# LIGHT-TDS.net
KiCad netlist of a schematic drawn in Altium Designer
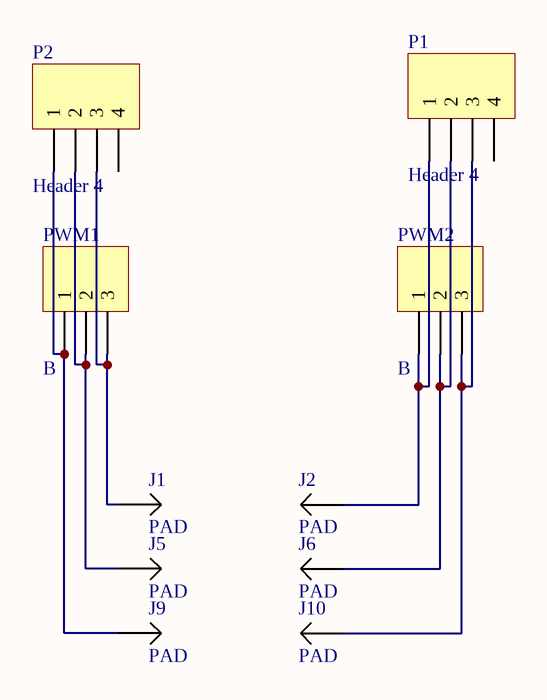
[diagram p0: LIGHT-TDS.SchDoc]

(export (version "E")
  (design (tool "Eeschema 10.0.6"))
  (components
    (comp (ref "J1")
      (value "PAD")
      (footprint "PAD")
      (description "Header 1")
      (fields (field (name "MF") "Connfly electronic (Zhenqin)") (field (name "MP") "PLS-3 (DS1021-1x3)"))
      (libsource (lib "lib") (part "PAD"))
    )
    (comp (ref "J2")
      (value "PAD")
      (footprint "PAD")
      (description "Header 1")
      (fields (field (name "MF") "Connfly electronic (Zhenqin)") (field (name "MP") "PLS-3 (DS1021-1x3)"))
      (libsource (lib "lib") (part "PAD"))
    )
    (comp (ref "J5")
      (value "PAD")
      (footprint "PAD")
      (description "Header 1")
      (fields (field (name "MF") "Connfly electronic (Zhenqin)") (field (name "MP") "PLS-3 (DS1021-1x3)"))
      (libsource (lib "lib") (part "PAD"))
    )
    (comp (ref "J6")
      (value "PAD")
      (footprint "PAD")
      (description "Header 1")
      (fields (field (name "MF") "Connfly electronic (Zhenqin)") (field (name "MP") "PLS-3 (DS1021-1x3)"))
      (libsource (lib "lib") (part "PAD"))
    )
    (comp (ref "J9")
      (value "PAD")
      (footprint "PAD")
      (description "Header 1")
      (fields (field (name "MF") "Connfly electronic (Zhenqin)") (field (name "MP") "PLS-3 (DS1021-1x3)"))
      (libsource (lib "lib") (part "PAD"))
    )
    (comp (ref "J10")
      (value "PAD")
      (footprint "PAD")
      (description "Header 1")
      (fields (field (name "MF") "Connfly electronic (Zhenqin)") (field (name "MP") "PLS-3 (DS1021-1x3)"))
      (libsource (lib "lib") (part "PAD"))
    )
    (comp (ref "P1")
      (value "Header 4")
      (footprint "HDR1X4")
      (description "Header, 4-Pin")
      (libsource (lib "lib") (part "Header 4"))
    )
    (comp (ref "P2")
      (value "Header 4")
      (footprint "HDR1X4")
      (description "Header, 4-Pin")
      (libsource (lib "lib") (part "Header 4"))
    )
    (comp (ref "PWM1")
      (value "B")
      (footprint "HDR Side 3 pin")
      (description "Header, 3-Pin")
      (fields (field (name "MF") "Connfly electronic (Zhenqin)") (field (name "MP") "PLS-3 (DS1021-1x3)"))
      (libsource (lib "DC_DC") (part "Header 3"))
    )
    (comp (ref "PWM2")
      (value "B")
      (footprint "HDR Side 3 pin")
      (description "Header, 3-Pin")
      (fields (field (name "MF") "Connfly electronic (Zhenqin)") (field (name "MP") "PLS-3 (DS1021-1x3)"))
      (libsource (lib "DC_DC") (part "Header 3"))
    )
  )
  (nets
    (net (code "1") (name "Net-(J1-Pad1)") (class "Default")
      (node (ref "J1") (pin "1") (pinfunction "1_1") (pintype "passive"))
      (node (ref "P2") (pin "3") (pinfunction "3_3") (pintype "passive"))
      (node (ref "PWM1") (pin "3") (pinfunction "3_3") (pintype "passive"))
    )
    (net (code "2") (name "Net-(J2-Pad1)") (class "Default")
      (node (ref "J2") (pin "1") (pinfunction "1_1") (pintype "passive"))
      (node (ref "P1") (pin "1") (pinfunction "1_1") (pintype "passive"))
      (node (ref "PWM2") (pin "1") (pinfunction "1_1") (pintype "passive"))
    )
    (net (code "3") (name "Net-(J5-Pad1)") (class "Default")
      (node (ref "J5") (pin "1") (pinfunction "1_1") (pintype "passive"))
      (node (ref "P2") (pin "2") (pinfunction "2_2") (pintype "passive"))
      (node (ref "PWM1") (pin "2") (pinfunction "2_2") (pintype "passive"))
    )
    (net (code "4") (name "Net-(J6-Pad1)") (class "Default")
      (node (ref "J6") (pin "1") (pinfunction "1_1") (pintype "passive"))
      (node (ref "P1") (pin "2") (pinfunction "2_2") (pintype "passive"))
      (node (ref "PWM2") (pin "2") (pinfunction "2_2") (pintype "passive"))
    )
    (net (code "5") (name "Net-(J9-Pad1)") (class "Default")
      (node (ref "J9") (pin "1") (pinfunction "1_1") (pintype "passive"))
      (node (ref "P2") (pin "1") (pinfunction "1_1") (pintype "passive"))
      (node (ref "PWM1") (pin "1") (pinfunction "1_1") (pintype "passive"))
    )
    (net (code "6") (name "Net-(J10-Pad1)") (class "Default")
      (node (ref "J10") (pin "1") (pinfunction "1_1") (pintype "passive"))
      (node (ref "P1") (pin "3") (pinfunction "3_3") (pintype "passive"))
      (node (ref "PWM2") (pin "3") (pinfunction "3_3") (pintype "passive"))
    )
    (net (code "7") (name "unconnected-(P1-Pad4)") (class "Default")
      (node (ref "P1") (pin "4") (pinfunction "4_4") (pintype "passive"))
    )
    (net (code "8") (name "unconnected-(P2-Pad4)") (class "Default")
      (node (ref "P2") (pin "4") (pinfunction "4_4") (pintype "passive"))
    )
  )
)
